# 8_h-bridge.net
KiCad netlist of a schematic drawn in Altium Designer
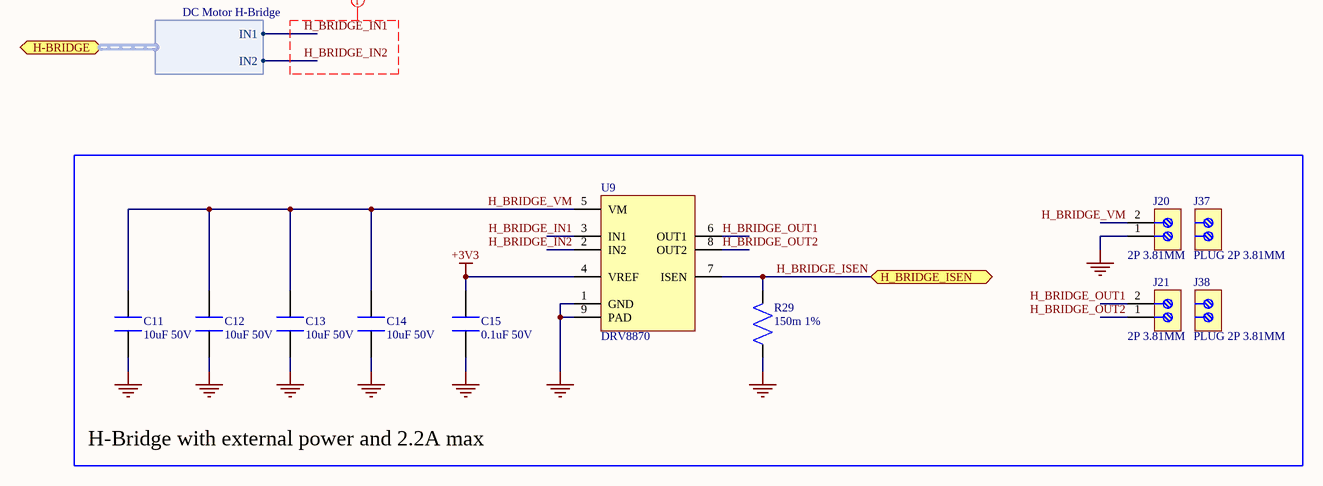
[diagram p0: 8_h-bridge.SchDoc]

(export (version "E")
  (design (tool "Eeschema 10.0.6"))
  (components
    (comp (ref "C11")
      (value "10uF 50V")
      (footprint "C0805")
      (description "X5R ±10% 50V 10uF 0805 Multilayer Ceramic Capacitors MLCC - SMD/SMT")
      (fields (field (name "LCSC PART") "C440198"))
      (libsource (lib "nombre_por_definir") (part "GRM21BR61H106KE43L"))
    )
    (comp (ref "C12")
      (value "10uF 50V")
      (footprint "C0805")
      (description "X5R ±10% 50V 10uF 0805 Multilayer Ceramic Capacitors MLCC - SMD/SMT")
      (fields (field (name "LCSC PART") "C440198"))
      (libsource (lib "nombre_por_definir") (part "GRM21BR61H106KE43L"))
    )
    (comp (ref "C13")
      (value "10uF 50V")
      (footprint "C0805")
      (description "X5R ±10% 50V 10uF 0805 Multilayer Ceramic Capacitors MLCC - SMD/SMT")
      (fields (field (name "LCSC PART") "C440198"))
      (libsource (lib "nombre_por_definir") (part "GRM21BR61H106KE43L"))
    )
    (comp (ref "C14")
      (value "10uF 50V")
      (footprint "C0805")
      (description "X5R ±10% 50V 10uF 0805 Multilayer Ceramic Capacitors MLCC - SMD/SMT")
      (fields (field (name "LCSC PART") "C440198"))
      (libsource (lib "nombre_por_definir") (part "GRM21BR61H106KE43L"))
    )
    (comp (ref "C15")
      (value "0.1uF 50V")
      (footprint "C0603")
      (description "X7R 100nF ±10% 50V 0603 Multilayer Ceramic Capacitors MLCC - SMD/SMT")
      (fields (field (name "LCSC PART") "C14663"))
      (libsource (lib "nombre_por_definir") (part "CC0603KRX7R9BB104"))
    )
    (comp (ref "J20")
      (value "2P 3.81MM")
      (footprint "TB-2P-3.81MM")
      (description "Terminal Block 2 Positions 3.81MM")
      (libsource (lib "nombre_por_definir") (part "TBLOCK-2P-3.81MM"))
    )
    (comp (ref "J21")
      (value "2P 3.81MM")
      (footprint "TB-2P-3.81MM")
      (description "Terminal Block 2 Positions 3.81MM")
      (libsource (lib "nombre_por_definir") (part "TBLOCK-2P-3.81MM"))
    )
    (comp (ref "J37")
      (value "PLUG 2P 3.81MM")
      (footprint "TB-PLUG-2P-3.81MM")
      (description "Terminal block plug 2positions 3.81mm")
      (libsource (lib "nombre_por_definir") (part "PLUG-2P-3.81MM"))
    )
    (comp (ref "J38")
      (value "PLUG 2P 3.81MM")
      (footprint "TB-PLUG-2P-3.81MM")
      (description "Terminal block plug 2positions 3.81mm")
      (libsource (lib "nombre_por_definir") (part "PLUG-2P-3.81MM"))
    )
    (comp (ref "R29")
      (value "150m 1%")
      (footprint "R2512")
      (description "±1% 0.15Ω ±50ppm/℃ 2W 2512 Current Sense Resistors/Shunt Resistors")
      (fields (field (name "LCSC PART") "C252673"))
      (libsource (lib "nombre_por_definir") (part "MA251220FR150FZ"))
    )
    (comp (ref "U9")
      (value "DRV8870")
      (footprint "HSOP-8")
      (description "HSOP-8 Motor Driver ICs")
      (fields (field (name "LCSC PART") "C86590"))
      (libsource (lib "nombre_por_definir") (part "DRV8870DDAR"))
    )
  )
  (nets
    (net (code "4") (name "+3V3") (class "Default")
      (node (ref "C15") (pin "1") (pinfunction "1_1") (pintype "passive"))
      (node (ref "U9") (pin "4") (pinfunction "VREF_4") (pintype "passive"))
    )
    (net (code "5") (name "/H_BRIDGE_IN1") (class "Default")
      (node (ref "U9") (pin "3") (pinfunction "IN1_3") (pintype "passive"))
    )
    (net (code "6") (name "/H_BRIDGE_IN2") (class "Default")
      (node (ref "U9") (pin "2") (pinfunction "IN2_2") (pintype "passive"))
    )
    (net (code "7") (name "/H_BRIDGE_ISEN") (class "Default")
      (node (ref "R29") (pin "2") (pinfunction "2_2") (pintype "passive"))
      (node (ref "U9") (pin "7") (pinfunction "ISEN_7") (pintype "passive"))
    )
    (net (code "8") (name "/H_BRIDGE_OUT1") (class "Default")
      (node (ref "J21") (pin "2") (pinfunction "2_2") (pintype "passive"))
      (node (ref "U9") (pin "6") (pinfunction "OUT1_6") (pintype "passive"))
    )
    (net (code "9") (name "/H_BRIDGE_OUT2") (class "Default")
      (node (ref "J21") (pin "1") (pinfunction "1_1") (pintype "passive"))
      (node (ref "U9") (pin "8") (pinfunction "OUT2_8") (pintype "passive"))
    )
    (net (code "10") (name "/H_BRIDGE_VM") (class "Default")
      (node (ref "C11") (pin "1") (pinfunction "1_1") (pintype "passive"))
      (node (ref "C12") (pin "1") (pinfunction "1_1") (pintype "passive"))
      (node (ref "C13") (pin "1") (pinfunction "1_1") (pintype "passive"))
      (node (ref "C14") (pin "1") (pinfunction "1_1") (pintype "passive"))
      (node (ref "J20") (pin "2") (pinfunction "2_2") (pintype "passive"))
      (node (ref "U9") (pin "5") (pinfunction "VM_5") (pintype "passive"))
    )
    (net (code "12") (name "GND") (class "Default")
      (node (ref "C11") (pin "2") (pinfunction "2_2") (pintype "passive"))
      (node (ref "C12") (pin "2") (pinfunction "2_2") (pintype "passive"))
      (node (ref "C13") (pin "2") (pinfunction "2_2") (pintype "passive"))
      (node (ref "C14") (pin "2") (pinfunction "2_2") (pintype "passive"))
      (node (ref "C15") (pin "2") (pinfunction "2_2") (pintype "passive"))
      (node (ref "J20") (pin "1") (pinfunction "1_1") (pintype "passive"))
      (node (ref "R29") (pin "1") (pinfunction "1_1") (pintype "passive"))
      (node (ref "U9") (pin "1") (pinfunction "GND_1") (pintype "passive"))
      (node (ref "U9") (pin "9") (pinfunction "PAD_9") (pintype "passive"))
    )
  )
)
